# SH4_-_MICROCONTROLLER.net
KiCad netlist of a schematic drawn in Altium Designer
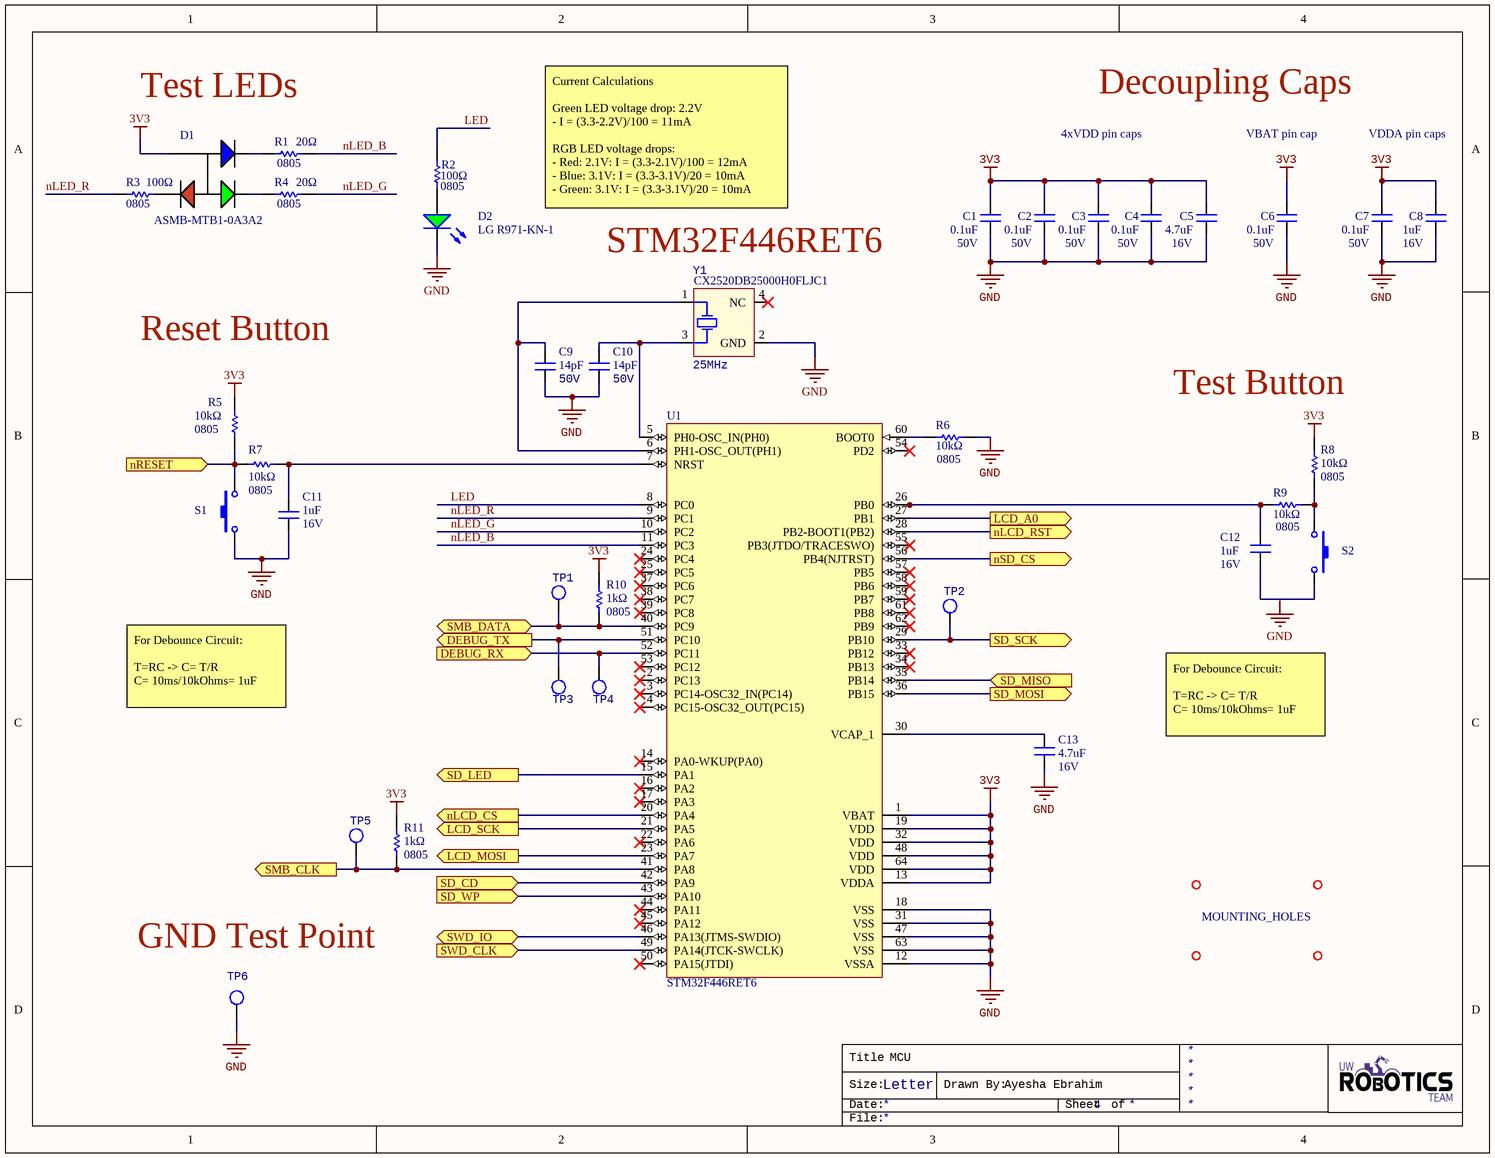
[diagram p0: SH4 - MICROCONTROLLER.SchDoc]

(export (version "E")
  (design (tool "Eeschema 10.0.6"))
  (components
    (comp (ref "C1")
      (value "0.1uF")
      (footprint "CAPC2012X140N")
      (description "CAP CER 0.1UF 50V X7R 0805")
      (fields
        (field (name "TOLERANCE") "10%")
        (field (name "VOLTAGE RATING") "50V")
        (field (name "Comment") "CAP_0.1uF_50V_0805")
      )
      (libsource (lib "UWRT_Schematic_Library_2020") (part "CAP_0.1uF_50V_0805"))
    )
    (comp (ref "C2")
      (value "0.1uF")
      (footprint "CAPC2012X140N")
      (description "CAP CER 0.1UF 50V X7R 0805")
      (fields
        (field (name "TOLERANCE") "10%")
        (field (name "VOLTAGE RATING") "50V")
        (field (name "Comment") "CAP_0.1uF_50V_0805")
      )
      (libsource (lib "UWRT_Schematic_Library_2020") (part "CAP_0.1uF_50V_0805"))
    )
    (comp (ref "C3")
      (value "0.1uF")
      (footprint "CAPC2012X140N")
      (description "CAP CER 0.1UF 50V X7R 0805")
      (fields
        (field (name "TOLERANCE") "10%")
        (field (name "VOLTAGE RATING") "50V")
        (field (name "Comment") "CAP_0.1uF_50V_0805")
      )
      (libsource (lib "UWRT_Schematic_Library_2020") (part "CAP_0.1uF_50V_0805"))
    )
    (comp (ref "C4")
      (value "0.1uF")
      (footprint "CAPC2012X140N")
      (description "CAP CER 0.1UF 50V X7R 0805")
      (fields
        (field (name "TOLERANCE") "10%")
        (field (name "VOLTAGE RATING") "50V")
        (field (name "Comment") "CAP_0.1uF_50V_0805")
      )
      (libsource (lib "UWRT_Schematic_Library_2020") (part "CAP_0.1uF_50V_0805"))
    )
    (comp (ref "C5")
      (value "4.7uF")
      (footprint "CAPC2012X140N")
      (description "CAP CER 4.7UF 16V X5R 0805")
      (fields
        (field (name "TOLERANCE") "10%")
        (field (name "VOLTAGE RATING") "16V")
        (field (name "Comment") "CAP_4.7uF_16V_0805")
      )
      (libsource (lib "UWRT_Schematic_Library_2020") (part "CAP_4.7uF_16V_0805"))
    )
    (comp (ref "C6")
      (value "0.1uF")
      (footprint "CAPC2012X140N")
      (description "CAP CER 0.1UF 50V X7R 0805")
      (fields
        (field (name "TOLERANCE") "10%")
        (field (name "VOLTAGE RATING") "50V")
        (field (name "Comment") "CAP_0.1uF_50V_0805")
      )
      (libsource (lib "UWRT_Schematic_Library_2020") (part "CAP_0.1uF_50V_0805"))
    )
    (comp (ref "C7")
      (value "0.1uF")
      (footprint "CAPC2012X140N")
      (description "CAP CER 0.1UF 50V X7R 0805")
      (fields
        (field (name "TOLERANCE") "10%")
        (field (name "VOLTAGE RATING") "50V")
        (field (name "Comment") "CAP_0.1uF_50V_0805")
      )
      (libsource (lib "UWRT_Schematic_Library_2020") (part "CAP_0.1uF_50V_0805"))
    )
    (comp (ref "C8")
      (value "1uF")
      (footprint "CAPC2012X140N")
      (description "CAP CER 1UF 16V X7R 0805")
      (fields
        (field (name "TOLERANCE") "10%")
        (field (name "VOLTAGE RATING") "16V")
        (field (name "Comment") "CAP_1uF_16V_0805")
      )
      (libsource (lib "UWRT_Schematic_Library_2020") (part "CAP_1uF_16V_0805"))
    )
    (comp (ref "C9")
      (value "14pF")
      (footprint "CAPC0603(1608)55_N")
      (description "Cap Ceramic 14pF 50V C0G 5% SMD 0603 125C Cardboard T/R")
      (fields
        (field (name "TOLERANCE") "5%")
        (field (name "VOLTAGE RATING (DC)") "50V")
        (field (name "Comment") "CL10C140JB8NNNC")
      )
      (libsource (lib "UWRT_Schematic_Library_2020") (part "CL10C140JB8NNNC"))
    )
    (comp (ref "C10")
      (value "14pF")
      (footprint "CAPC0603(1608)55_N")
      (description "Cap Ceramic 14pF 50V C0G 5% SMD 0603 125C Cardboard T/R")
      (fields
        (field (name "TOLERANCE") "5%")
        (field (name "VOLTAGE RATING (DC)") "50V")
        (field (name "Comment") "CL10C140JB8NNNC")
      )
      (libsource (lib "UWRT_Schematic_Library_2020") (part "CL10C140JB8NNNC"))
    )
    (comp (ref "C11")
      (value "1uF")
      (footprint "CAPC2012X140N")
      (description "CAP CER 1UF 16V X7R 0805")
      (fields
        (field (name "TOLERANCE") "10%")
        (field (name "VOLTAGE RATING") "16V")
        (field (name "Comment") "CAP_1uF_16V_0805")
      )
      (libsource (lib "UWRT_Schematic_Library_2020") (part "CAP_1uF_16V_0805"))
    )
    (comp (ref "C12")
      (value "1uF")
      (footprint "CAPC2012X140N")
      (description "CAP CER 1UF 16V X7R 0805")
      (fields
        (field (name "TOLERANCE") "10%")
        (field (name "VOLTAGE RATING") "16V")
        (field (name "Comment") "CAP_1uF_16V_0805")
      )
      (libsource (lib "UWRT_Schematic_Library_2020") (part "CAP_1uF_16V_0805"))
    )
    (comp (ref "C13")
      (value "4.7uF")
      (footprint "CAPC2012X140N")
      (description "CAP CER 4.7UF 16V X5R 0805")
      (fields
        (field (name "TOLERANCE") "10%")
        (field (name "VOLTAGE RATING") "16V")
        (field (name "Comment") "CAP_4.7uF_16V_0805")
      )
      (libsource (lib "UWRT_Schematic_Library_2020") (part "CAP_4.7uF_16V_0805"))
    )
    (comp (ref "D1")
      (value "LED_RGB")
      (footprint "LED_RGB")
      (description "LED RGB DIFFUSED 4PLCC SMD")
      (fields (field (name "MANUFACTURER PART NUMBER 1") "ASMB-MTB1-0A3A2"))
      (libsource (lib "UWRT_Schematic_Library_2020") (part "LED_RGB"))
    )
    (comp (ref "D2")
      (value "DIO_LED_G")
      (footprint "LED_0805_LINE")
      (description "LED GREEN DIFFUSED 0805 SMD")
      (fields (field (name "MANUFACTURER PART NUMBER 1") "LG R971-KN-1"))
      (libsource (lib "UWRT_Schematic_Library_2020") (part "DIO_LED_G"))
    )
    (comp (ref "MH1")
      (value "MOUNTING_HOLES")
      (footprint "MOUNTING_HOLE")
      (description "6cm x 6cm")
      (libsource (lib "UWRT_Schematic_Library_2020") (part "MOUNTING_HOLES"))
    )
    (comp (ref "MH2")
      (value "MOUNTING_HOLES")
      (footprint "MOUNTING_HOLE")
      (description "6cm x 6cm")
      (libsource (lib "UWRT_Schematic_Library_2020") (part "MOUNTING_HOLES"))
    )
    (comp (ref "MH3")
      (value "MOUNTING_HOLES")
      (footprint "MOUNTING_HOLE")
      (description "6cm x 6cm")
      (libsource (lib "UWRT_Schematic_Library_2020") (part "MOUNTING_HOLES"))
    )
    (comp (ref "MH4")
      (value "MOUNTING_HOLES")
      (footprint "MOUNTING_HOLE")
      (description "6cm x 6cm")
      (libsource (lib "UWRT_Schematic_Library_2020") (part "MOUNTING_HOLES"))
    )
    (comp (ref "R1")
      (value "20Ω")
      (footprint "RESC2012X60N")
      (description "RES SMD 20 OHM 1% 1/8W 0805")
      (fields
        (field (name "CASE CODE (IMPERIAL)") "0805")
        (field (name "TOLERANCE") "1%")
        (field (name "Comment") "RES_20Ω_0805")
      )
      (libsource (lib "UWRT_Schematic_Library_2020") (part "RES_20Ω_0805"))
    )
    (comp (ref "R2")
      (value "100Ω")
      (footprint "RESC2012X60N")
      (description "RES SMD 100 OHM 1% 1/8W 0805")
      (fields (field (name "CASE CODE (IMPERIAL)") "0805") (field (name "Comment") "RES_100Ω_0805"))
      (libsource (lib "UWRT_Schematic_Library_2020") (part "RES_100Ω_0805"))
    )
    (comp (ref "R3")
      (value "100Ω")
      (footprint "RESC2012X60N")
      (description "RES SMD 100 OHM 1% 1/8W 0805")
      (fields (field (name "CASE CODE (IMPERIAL)") "0805") (field (name "Comment") "RES_100Ω_0805"))
      (libsource (lib "UWRT_Schematic_Library_2020") (part "RES_100Ω_0805"))
    )
    (comp (ref "R4")
      (value "20Ω")
      (footprint "RESC2012X60N")
      (description "RES SMD 20 OHM 1% 1/8W 0805")
      (fields
        (field (name "CASE CODE (IMPERIAL)") "0805")
        (field (name "TOLERANCE") "1%")
        (field (name "Comment") "RES_20Ω_0805")
      )
      (libsource (lib "UWRT_Schematic_Library_2020") (part "RES_20Ω_0805"))
    )
    (comp (ref "R5")
      (value "10kΩ")
      (footprint "RESC2012X60N")
      (description "RES SMD 10K OHM 1% 1/8W 0805")
      (fields
        (field (name "CASE CODE (IMPERIAL)") "0805")
        (field (name "TOLERANCE") "1%")
        (field (name "Comment") "RES_10kΩ_0805")
      )
      (libsource (lib "UWRT_Schematic_Library_2020") (part "RES_10kΩ_0805"))
    )
    (comp (ref "R6")
      (value "10kΩ")
      (footprint "RESC2012X60N")
      (description "RES SMD 10K OHM 1% 1/8W 0805")
      (fields
        (field (name "CASE CODE (IMPERIAL)") "0805")
        (field (name "TOLERANCE") "1%")
        (field (name "Comment") "RES_10kΩ_0805")
      )
      (libsource (lib "UWRT_Schematic_Library_2020") (part "RES_10kΩ_0805"))
    )
    (comp (ref "R7")
      (value "10kΩ")
      (footprint "RESC2012X60N")
      (description "RES SMD 10K OHM 1% 1/8W 0805")
      (fields
        (field (name "CASE CODE (IMPERIAL)") "0805")
        (field (name "TOLERANCE") "1%")
        (field (name "Comment") "RES_10kΩ_0805")
      )
      (libsource (lib "UWRT_Schematic_Library_2020") (part "RES_10kΩ_0805"))
    )
    (comp (ref "R8")
      (value "10kΩ")
      (footprint "RESC2012X60N")
      (description "RES SMD 10K OHM 1% 1/8W 0805")
      (fields
        (field (name "CASE CODE (IMPERIAL)") "0805")
        (field (name "TOLERANCE") "1%")
        (field (name "Comment") "RES_10kΩ_0805")
      )
      (libsource (lib "UWRT_Schematic_Library_2020") (part "RES_10kΩ_0805"))
    )
    (comp (ref "R9")
      (value "10kΩ")
      (footprint "RESC2012X60N")
      (description "RES SMD 10K OHM 1% 1/8W 0805")
      (fields
        (field (name "CASE CODE (IMPERIAL)") "0805")
        (field (name "TOLERANCE") "1%")
        (field (name "Comment") "RES_10kΩ_0805")
      )
      (libsource (lib "UWRT_Schematic_Library_2020") (part "RES_10kΩ_0805"))
    )
    (comp (ref "R10")
      (value "1kΩ")
      (footprint "RESC2012X60N")
      (description "RES SMD 1K OHM 1% 1/8W 0805")
      (fields
        (field (name "CASE CODE (IMPERIAL)") "0805")
        (field (name "TOLERANCE") "1%")
        (field (name "Comment") "RES_1kΩ_0805")
      )
      (libsource (lib "UWRT_Schematic_Library_2020") (part "RES_1kΩ_0805"))
    )
    (comp (ref "R11")
      (value "1kΩ")
      (footprint "RESC2012X60N")
      (description "RES SMD 1K OHM 1% 1/8W 0805")
      (fields
        (field (name "CASE CODE (IMPERIAL)") "0805")
        (field (name "TOLERANCE") "1%")
        (field (name "Comment") "RES_1kΩ_0805")
      )
      (libsource (lib "UWRT_Schematic_Library_2020") (part "RES_1kΩ_0805"))
    )
    (comp (ref "S1")
      (value "SW_TACTILE")
      (footprint "B3U-1000P")
      (description "Tactile Switch (Grey)")
      (libsource (lib "UWRT_Schematic_Library_2020") (part "SW_TACTILE"))
    )
    (comp (ref "S2")
      (value "SW_TACTILE")
      (footprint "B3U-1000P")
      (description "Tactile Switch (Grey)")
      (libsource (lib "UWRT_Schematic_Library_2020") (part "SW_TACTILE"))
    )
    (comp (ref "TP1")
      (value "TESTPOINT_LOOP")
      (footprint "TESTPOINT_LOOP")
      (description "Loop testpoint through-hole pad")
      (libsource (lib "UWRT_Schematic_Library_2020") (part "TESTPOINT_LOOP"))
    )
    (comp (ref "TP2")
      (value "TESTPOINT_LOOP")
      (footprint "TESTPOINT_LOOP")
      (description "Loop testpoint through-hole pad")
      (libsource (lib "UWRT_Schematic_Library_2020") (part "TESTPOINT_LOOP"))
    )
    (comp (ref "TP3")
      (value "TESTPOINT_LOOP")
      (footprint "TESTPOINT_LOOP")
      (description "Loop testpoint through-hole pad")
      (libsource (lib "UWRT_Schematic_Library_2020") (part "TESTPOINT_LOOP"))
    )
    (comp (ref "TP4")
      (value "TESTPOINT_LOOP")
      (footprint "TESTPOINT_LOOP")
      (description "Loop testpoint through-hole pad")
      (libsource (lib "UWRT_Schematic_Library_2020") (part "TESTPOINT_LOOP"))
    )
    (comp (ref "TP5")
      (value "TESTPOINT_LOOP")
      (footprint "TESTPOINT_LOOP")
      (description "Loop testpoint through-hole pad")
      (libsource (lib "UWRT_Schematic_Library_2020") (part "TESTPOINT_LOOP"))
    )
    (comp (ref "TP6")
      (value "TESTPOINT_LOOP")
      (footprint "TESTPOINT_LOOP")
      (description "Loop testpoint through-hole pad")
      (libsource (lib "UWRT_Schematic_Library_2020") (part "TESTPOINT_LOOP"))
    )
    (comp (ref "U1")
      (value "STM32F446RET6")
      (footprint "STM-LQFP64_L")
      (libsource (lib "UWRT_Schematic_Library_2020") (part "MCU_STM32F446RET6"))
    )
    (comp (ref "Y1")
      (value "CRYSTAL_25MHZ")
      (footprint "SOIC254P1016X440-4N")
      (description "CRYSTAL 25.0000MHZ 12PF SMD")
      (fields
        (field (name "MANUFACTURER PART NUMBER 1") "CX2520DB25000H0FLJC1")
        (field (name "FREQUENCY") "25MHz")
      )
      (libsource (lib "UWRT_Schematic_Library_2020") (part "CRYSTAL_25MHZ"))
    )
  )
  (nets
    (net (code "1") (name "/DEBUG_RX") (class "Default")
      (node (ref "TP4") (pin "1") (pintype "passive"))
      (node (ref "U1") (pin "52") (pinfunction "PC11_52") (pintype "bidirectional"))
    )
    (net (code "2") (name "/DEBUG_TX") (class "Default")
      (node (ref "TP3") (pin "1") (pintype "passive"))
      (node (ref "U1") (pin "51") (pinfunction "PC10_51") (pintype "bidirectional"))
    )
    (net (code "3") (name "/LCD_A0") (class "Default")
      (node (ref "U1") (pin "27") (pinfunction "PB1_27") (pintype "bidirectional"))
    )
    (net (code "4") (name "/LCD_MOSI") (class "Default")
      (node (ref "U1") (pin "23") (pinfunction "PA7_23") (pintype "bidirectional"))
    )
    (net (code "5") (name "/LCD_SCK") (class "Default")
      (node (ref "U1") (pin "21") (pinfunction "PA5_21") (pintype "bidirectional"))
    )
    (net (code "6") (name "/LED") (class "Default")
      (node (ref "R2") (pin "2") (pinfunction "2_2") (pintype "passive"))
      (node (ref "U1") (pin "8") (pinfunction "PC0_8") (pintype "bidirectional"))
    )
    (net (code "7") (name "/SD_CD") (class "Default")
      (node (ref "U1") (pin "42") (pinfunction "PA9_42") (pintype "bidirectional"))
    )
    (net (code "8") (name "/SD_LED") (class "Default")
      (node (ref "U1") (pin "15") (pinfunction "PA1_15") (pintype "bidirectional"))
    )
    (net (code "9") (name "/SD_MISO") (class "Default")
      (node (ref "U1") (pin "35") (pinfunction "PB14_35") (pintype "bidirectional"))
    )
    (net (code "10") (name "/SD_MOSI") (class "Default")
      (node (ref "U1") (pin "36") (pinfunction "PB15_36") (pintype "bidirectional"))
    )
    (net (code "11") (name "/SD_SCK") (class "Default")
      (node (ref "TP2") (pin "1") (pintype "passive"))
      (node (ref "U1") (pin "29") (pinfunction "PB10_29") (pintype "bidirectional"))
    )
    (net (code "12") (name "/SD_WP") (class "Default")
      (node (ref "U1") (pin "43") (pinfunction "PA10_43") (pintype "bidirectional"))
    )
    (net (code "13") (name "/SMB_CLK") (class "Default")
      (node (ref "R11") (pin "1") (pinfunction "1_1") (pintype "passive"))
      (node (ref "TP5") (pin "1") (pintype "passive"))
      (node (ref "U1") (pin "41") (pinfunction "PA8_41") (pintype "bidirectional"))
    )
    (net (code "14") (name "/SMB_DATA") (class "Default")
      (node (ref "R10") (pin "1") (pinfunction "1_1") (pintype "passive"))
      (node (ref "TP1") (pin "1") (pintype "passive"))
      (node (ref "U1") (pin "40") (pinfunction "PC9_40") (pintype "bidirectional"))
    )
    (net (code "15") (name "/SWD_CLK") (class "Default")
      (node (ref "U1") (pin "49") (pinfunction "PA14(JTCK-SWCLK)_49") (pintype "bidirectional"))
    )
    (net (code "16") (name "/SWD_IO") (class "Default")
      (node (ref "U1") (pin "46") (pinfunction "PA13(JTMS-SWDIO)_46") (pintype "bidirectional"))
    )
    (net (code "17") (name "/nLCD_CS") (class "Default")
      (node (ref "U1") (pin "20") (pinfunction "PA4_20") (pintype "bidirectional"))
    )
    (net (code "18") (name "/nLCD_RST") (class "Default")
      (node (ref "U1") (pin "28") (pinfunction "PB2-BOOT1(PB2)_28") (pintype "bidirectional"))
    )
    (net (code "19") (name "/nLED_B") (class "Default")
      (node (ref "R1") (pin "2") (pinfunction "2_2") (pintype "passive"))
      (node (ref "U1") (pin "11") (pinfunction "PC3_11") (pintype "bidirectional"))
    )
    (net (code "20") (name "/nLED_G") (class "Default")
      (node (ref "R4") (pin "2") (pinfunction "2_2") (pintype "passive"))
      (node (ref "U1") (pin "10") (pinfunction "PC2_10") (pintype "bidirectional"))
    )
    (net (code "21") (name "/nLED_R") (class "Default")
      (node (ref "R3") (pin "1") (pinfunction "1_1") (pintype "passive"))
      (node (ref "U1") (pin "9") (pinfunction "PC1_9") (pintype "bidirectional"))
    )
    (net (code "22") (name "/nRESET") (class "Default")
      (node (ref "R5") (pin "1") (pinfunction "1_1") (pintype "passive"))
      (node (ref "R7") (pin "1") (pinfunction "1_1") (pintype "passive"))
      (node (ref "S1") (pin "2") (pinfunction "2_2") (pintype "passive"))
    )
    (net (code "23") (name "/nSD_CS") (class "Default")
      (node (ref "U1") (pin "56") (pinfunction "PB4(NJTRST)_56") (pintype "bidirectional"))
    )
    (net (code "24") (name "3V3") (class "Default")
      (node (ref "C1") (pin "2") (pinfunction "2_2") (pintype "passive"))
      (node (ref "C2") (pin "2") (pinfunction "2_2") (pintype "passive"))
      (node (ref "C3") (pin "2") (pinfunction "2_2") (pintype "passive"))
      (node (ref "C4") (pin "2") (pinfunction "2_2") (pintype "passive"))
      (node (ref "C5") (pin "2") (pinfunction "2_2") (pintype "passive"))
      (node (ref "C6") (pin "2") (pinfunction "2_2") (pintype "passive"))
      (node (ref "C7") (pin "2") (pinfunction "2_2") (pintype "passive"))
      (node (ref "C8") (pin "2") (pinfunction "2_2") (pintype "passive"))
      (node (ref "D1") (pin "4") (pinfunction "9_4") (pintype "passive"))
      (node (ref "R10") (pin "2") (pinfunction "2_2") (pintype "passive"))
      (node (ref "R11") (pin "2") (pinfunction "2_2") (pintype "passive"))
      (node (ref "R5") (pin "2") (pinfunction "2_2") (pintype "passive"))
      (node (ref "R8") (pin "2") (pinfunction "2_2") (pintype "passive"))
      (node (ref "U1") (pin "1") (pinfunction "VBAT_1") (pintype "power_in"))
      (node (ref "U1") (pin "13") (pinfunction "VDDA_13") (pintype "power_in"))
      (node (ref "U1") (pin "19") (pinfunction "VDD_19") (pintype "power_in"))
      (node (ref "U1") (pin "32") (pinfunction "VDD_32") (pintype "power_in"))
      (node (ref "U1") (pin "48") (pinfunction "VDD_48") (pintype "power_in"))
      (node (ref "U1") (pin "64") (pinfunction "VDD_64") (pintype "power_in"))
    )
    (net (code "25") (name "GND") (class "Default")
      (node (ref "C1") (pin "1") (pinfunction "1_1") (pintype "passive"))
      (node (ref "C10") (pin "1") (pinfunction "1_1") (pintype "passive"))
      (node (ref "C11") (pin "1") (pinfunction "1_1") (pintype "passive"))
      (node (ref "C13") (pin "1") (pinfunction "1_1") (pintype "passive"))
      (node (ref "C2") (pin "1") (pinfunction "1_1") (pintype "passive"))
      (node (ref "C3") (pin "1") (pinfunction "1_1") (pintype "passive"))
      (node (ref "C4") (pin "1") (pinfunction "1_1") (pintype "passive"))
      (node (ref "C5") (pin "1") (pinfunction "1_1") (pintype "passive"))
      (node (ref "C6") (pin "1") (pinfunction "1_1") (pintype "passive"))
      (node (ref "C7") (pin "1") (pinfunction "1_1") (pintype "passive"))
      (node (ref "C8") (pin "1") (pinfunction "1_1") (pintype "passive"))
      (node (ref "C9") (pin "1") (pinfunction "1_1") (pintype "passive"))
      (node (ref "D2") (pin "2") (pinfunction "K_2") (pintype "passive"))
      (node (ref "R6") (pin "2") (pinfunction "2_2") (pintype "passive"))
      (node (ref "S1") (pin "1") (pinfunction "1_1") (pintype "passive"))
      (node (ref "TP6") (pin "1") (pintype "passive"))
      (node (ref "U1") (pin "12") (pinfunction "VSSA_12") (pintype "power_in"))
      (node (ref "U1") (pin "18") (pinfunction "VSS_18") (pintype "power_in"))
      (node (ref "U1") (pin "31") (pinfunction "VSS_31") (pintype "power_in"))
      (node (ref "U1") (pin "47") (pinfunction "VSS_47") (pintype "power_in"))
      (node (ref "U1") (pin "63") (pinfunction "VSS_63") (pintype "power_in"))
      (node (ref "Y1") (pin "2") (pinfunction "GND_2") (pintype "power_in"))
    )
    (net (code "26") (name "Net-(C12-Pad1)") (class "Default")
      (node (ref "C12") (pin "1") (pinfunction "1_1") (pintype "passive"))
      (node (ref "S2") (pin "2") (pinfunction "2_2") (pintype "passive"))
    )
    (net (code "27") (name "Net-(D1-10)") (class "Default")
      (node (ref "D1") (pin "3") (pinfunction "10_3") (pintype "passive"))
      (node (ref "R1") (pin "1") (pinfunction "1_1") (pintype "passive"))
    )
    (net (code "28") (name "Net-(D1-11)") (class "Default")
      (node (ref "D1") (pin "1") (pinfunction "11_1") (pintype "passive"))
      (node (ref "R3") (pin "2") (pinfunction "2_2") (pintype "passive"))
    )
    (net (code "29") (name "Net-(D1-12)") (class "Default")
      (node (ref "D1") (pin "2") (pinfunction "12_2") (pintype "passive"))
      (node (ref "R4") (pin "1") (pinfunction "1_1") (pintype "passive"))
    )
    (net (code "30") (name "Net-(D2-A)") (class "Default")
      (node (ref "D2") (pin "1") (pinfunction "A_1") (pintype "passive"))
      (node (ref "R2") (pin "1") (pinfunction "1_1") (pintype "passive"))
    )
    (net (code "31") (name "Net-(R8-Pad1)") (class "Default")
      (node (ref "R8") (pin "1") (pinfunction "1_1") (pintype "passive"))
      (node (ref "R9") (pin "2") (pinfunction "2_2") (pintype "passive"))
      (node (ref "S2") (pin "1") (pinfunction "1_1") (pintype "passive"))
    )
    (net (code "32") (name "Net-(U1-BOOT0)") (class "Default")
      (node (ref "R6") (pin "1") (pinfunction "1_1") (pintype "passive"))
      (node (ref "U1") (pin "60") (pinfunction "BOOT0_60") (pintype "input"))
    )
    (net (code "33") (name "Net-(U1-NRST)") (class "Default")
      (node (ref "C11") (pin "2") (pinfunction "2_2") (pintype "passive"))
      (node (ref "R7") (pin "2") (pinfunction "2_2") (pintype "passive"))
      (node (ref "U1") (pin "7") (pinfunction "NRST_7") (pintype "bidirectional"))
    )
    (net (code "34") (name "Net-(U1-PB0)") (class "Default")
      (node (ref "C12") (pin "2") (pinfunction "2_2") (pintype "passive"))
      (node (ref "R9") (pin "1") (pinfunction "1_1") (pintype "passive"))
      (node (ref "U1") (pin "26") (pinfunction "PB0_26") (pintype "bidirectional"))
    )
    (net (code "35") (name "Net-(U1-PH0-OSC_IN(PH0))") (class "Default")
      (node (ref "C10") (pin "2") (pinfunction "2_2") (pintype "passive"))
      (node (ref "U1") (pin "5") (pinfunction "PH0-OSC_IN(PH0)_5") (pintype "bidirectional"))
      (node (ref "Y1") (pin "3") (pinfunction "HOT_3") (pintype "passive"))
    )
    (net (code "36") (name "Net-(U1-PH1-OSC_OUT(PH1))") (class "Default")
      (node (ref "C9") (pin "2") (pinfunction "2_2") (pintype "passive"))
      (node (ref "U1") (pin "6") (pinfunction "PH1-OSC_OUT(PH1)_6") (pintype "bidirectional"))
      (node (ref "Y1") (pin "1") (pinfunction "HOT_1") (pintype "passive"))
    )
    (net (code "37") (name "Net-(U1-VCAP_1)") (class "Default")
      (node (ref "C13") (pin "2") (pinfunction "2_2") (pintype "passive"))
      (node (ref "U1") (pin "30") (pinfunction "VCAP_1_30") (pintype "passive"))
    )
    (net (code "38") (name "unconnected-(U1-PA0-WKUP(PA0)-Pad14)") (class "Default")
      (node (ref "U1") (pin "14") (pinfunction "PA0-WKUP(PA0)_14") (pintype "bidirectional+no_connect"))
    )
    (net (code "39") (name "unconnected-(U1-PA2-Pad16)") (class "Default")
      (node (ref "U1") (pin "16") (pinfunction "PA2_16") (pintype "bidirectional+no_connect"))
    )
    (net (code "40") (name "unconnected-(U1-PA3-Pad17)") (class "Default")
      (node (ref "U1") (pin "17") (pinfunction "PA3_17") (pintype "bidirectional+no_connect"))
    )
    (net (code "41") (name "unconnected-(U1-PA6-Pad22)") (class "Default")
      (node (ref "U1") (pin "22") (pinfunction "PA6_22") (pintype "bidirectional+no_connect"))
    )
    (net (code "42") (name "unconnected-(U1-PA11-Pad44)") (class "Default")
      (node (ref "U1") (pin "44") (pinfunction "PA11_44") (pintype "bidirectional+no_connect"))
    )
    (net (code "43") (name "unconnected-(U1-PA12-Pad45)") (class "Default")
      (node (ref "U1") (pin "45") (pinfunction "PA12_45") (pintype "bidirectional+no_connect"))
    )
    (net (code "44") (name "unconnected-(U1-PA15(JTDI)-Pad50)") (class "Default")
      (node (ref "U1") (pin "50") (pinfunction "PA15(JTDI)_50") (pintype "bidirectional+no_connect"))
    )
    (net (code "45") (name "unconnected-(U1-PB3(JTDO{slash}TRACESWO)-Pad55)") (class "Default")
      (node (ref "U1") (pin "55") (pinfunction "PB3(JTDO/TRACESWO)_55") (pintype "bidirectional+no_connect"))
    )
    (net (code "46") (name "unconnected-(U1-PB5-Pad57)") (class "Default")
      (node (ref "U1") (pin "57") (pinfunction "PB5_57") (pintype "bidirectional+no_connect"))
    )
    (net (code "47") (name "unconnected-(U1-PB6-Pad58)") (class "Default")
      (node (ref "U1") (pin "58") (pinfunction "PB6_58") (pintype "bidirectional+no_connect"))
    )
    (net (code "48") (name "unconnected-(U1-PB7-Pad59)") (class "Default")
      (node (ref "U1") (pin "59") (pinfunction "PB7_59") (pintype "bidirectional+no_connect"))
    )
    (net (code "49") (name "unconnected-(U1-PB8-Pad61)") (class "Default")
      (node (ref "U1") (pin "61") (pinfunction "PB8_61") (pintype "bidirectional+no_connect"))
    )
    (net (code "50") (name "unconnected-(U1-PB9-Pad62)") (class "Default")
      (node (ref "U1") (pin "62") (pinfunction "PB9_62") (pintype "bidirectional+no_connect"))
    )
    (net (code "51") (name "unconnected-(U1-PB12-Pad33)") (class "Default")
      (node (ref "U1") (pin "33") (pinfunction "PB12_33") (pintype "bidirectional+no_connect"))
    )
    (net (code "52") (name "unconnected-(U1-PB13-Pad34)") (class "Default")
      (node (ref "U1") (pin "34") (pinfunction "PB13_34") (pintype "bidirectional+no_connect"))
    )
    (net (code "53") (name "unconnected-(U1-PC4-Pad24)") (class "Default")
      (node (ref "U1") (pin "24") (pinfunction "PC4_24") (pintype "bidirectional+no_connect"))
    )
    (net (code "54") (name "unconnected-(U1-PC5-Pad25)") (class "Default")
      (node (ref "U1") (pin "25") (pinfunction "PC5_25") (pintype "bidirectional+no_connect"))
    )
    (net (code "55") (name "unconnected-(U1-PC6-Pad37)") (class "Default")
      (node (ref "U1") (pin "37") (pinfunction "PC6_37") (pintype "bidirectional+no_connect"))
    )
    (net (code "56") (name "unconnected-(U1-PC7-Pad38)") (class "Default")
      (node (ref "U1") (pin "38") (pinfunction "PC7_38") (pintype "bidirectional+no_connect"))
    )
    (net (code "57") (name "unconnected-(U1-PC8-Pad39)") (class "Default")
      (node (ref "U1") (pin "39") (pinfunction "PC8_39") (pintype "bidirectional+no_connect"))
    )
    (net (code "58") (name "unconnected-(U1-PC12-Pad53)") (class "Default")
      (node (ref "U1") (pin "53") (pinfunction "PC12_53") (pintype "bidirectional+no_connect"))
    )
    (net (code "59") (name "unconnected-(U1-PC13-Pad2)") (class "Default")
      (node (ref "U1") (pin "2") (pinfunction "PC13_2") (pintype "bidirectional+no_connect"))
    )
    (net (code "60") (name "unconnected-(U1-PC14-OSC32_IN(PC14)-Pad3)") (class "Default")
      (node (ref "U1") (pin "3") (pinfunction "PC14-OSC32_IN(PC14)_3") (pintype "bidirectional+no_connect"))
    )
    (net (code "61") (name "unconnected-(U1-PC15-OSC32_OUT(PC15)-Pad4)") (class "Default")
      (node (ref "U1") (pin "4") (pinfunction "PC15-OSC32_OUT(PC15)_4") (pintype "bidirectional+no_connect"))
    )
    (net (code "62") (name "unconnected-(U1-PD2-Pad54)") (class "Default")
      (node (ref "U1") (pin "54") (pinfunction "PD2_54") (pintype "bidirectional+no_connect"))
    )
    (net (code "63") (name "unconnected-(Y1-NC-Pad4)") (class "Default")
      (node (ref "Y1") (pin "4") (pinfunction "NC_4") (pintype "passive+no_connect"))
    )
  )
)
